# Adafruit_VL53L0X.net
KiCad netlist of a schematic drawn in EAGLE
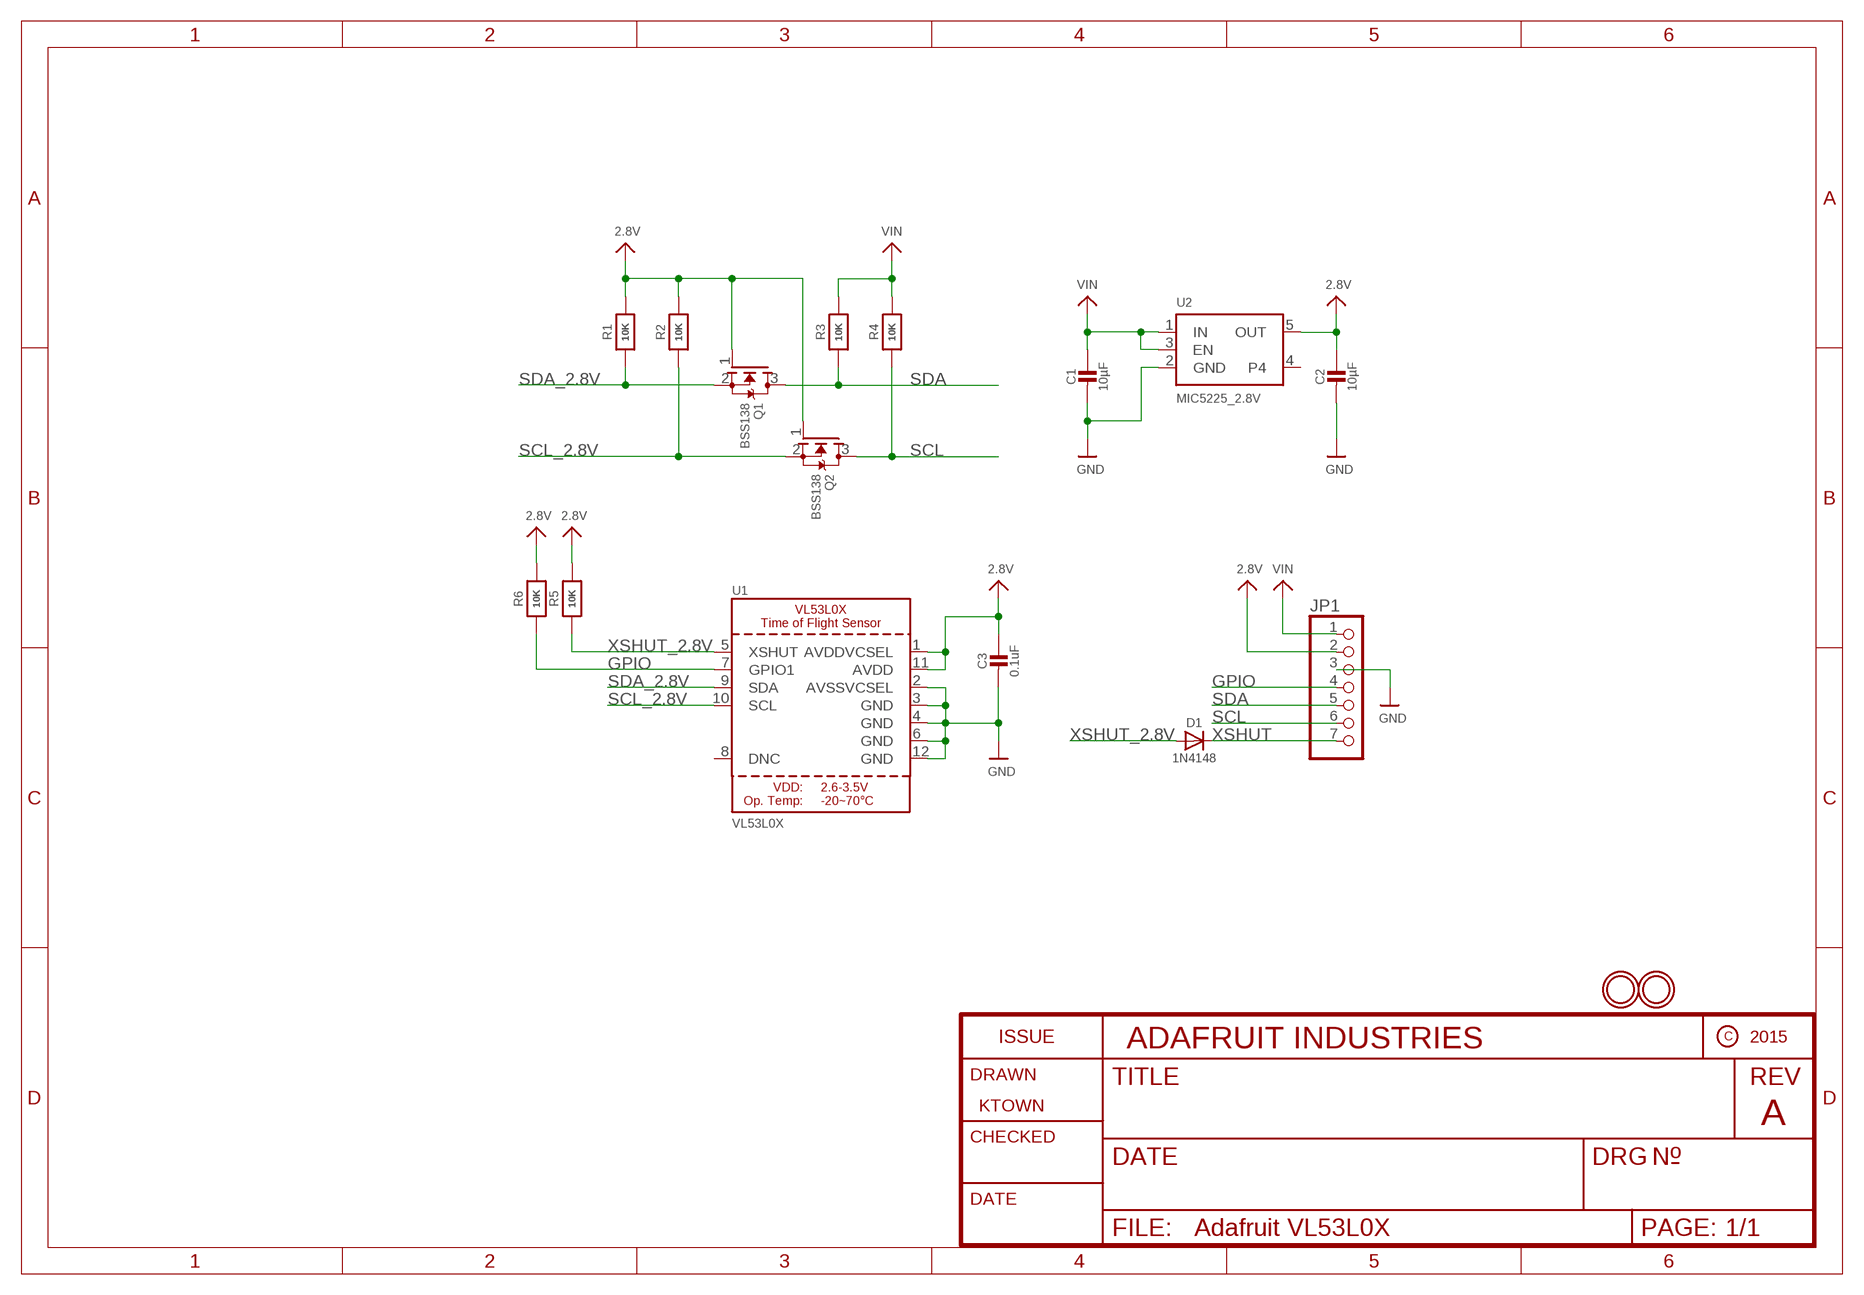
[diagram p0: schematic, sheet 1]

(export (version "E")
  (design (tool "Eeschema 10.0.6"))
  (components
    (comp (ref "C1")
      (value "10µF")
      (footprint "eagle-import:0805-NO")
      (libsource (lib "eagle-import") (part "CAP_CERAMIC0805-NOOUTLINE"))
    )
    (comp (ref "C2")
      (value "10µF")
      (footprint "eagle-import:0805-NO")
      (libsource (lib "eagle-import") (part "CAP_CERAMIC0805-NOOUTLINE"))
    )
    (comp (ref "C3")
      (value "0.1uF")
      (footprint "eagle-import:0805-NO")
      (libsource (lib "eagle-import") (part "CAP_CERAMIC0805-NOOUTLINE"))
    )
    (comp (ref "D1")
      (value "1N4148")
      (footprint "eagle-import:SOD-323")
      (libsource (lib "eagle-import") (part "DIODESOD-323"))
    )
    (comp (ref "JP1")
      (value "HEADER-1X770MIL")
      (footprint "eagle-import:1X07_ROUND_70")
      (libsource (lib "eagle-import") (part "HEADER-1X770MIL"))
    )
    (comp (ref "Q1")
      (value "BSS138")
      (footprint "eagle-import:SOT23-WIDE")
      (libsource (lib "eagle-import") (part "MOSFET-NWIDE"))
    )
    (comp (ref "Q2")
      (value "BSS138")
      (footprint "eagle-import:SOT23-WIDE")
      (libsource (lib "eagle-import") (part "MOSFET-NWIDE"))
    )
    (comp (ref "R1")
      (value "10K")
      (footprint "eagle-import:0805-NO")
      (libsource (lib "eagle-import") (part "RESISTOR0805_NOOUTLINE"))
    )
    (comp (ref "R2")
      (value "10K")
      (footprint "eagle-import:0805-NO")
      (libsource (lib "eagle-import") (part "RESISTOR0805_NOOUTLINE"))
    )
    (comp (ref "R3")
      (value "10K")
      (footprint "eagle-import:0805-NO")
      (libsource (lib "eagle-import") (part "RESISTOR0805_NOOUTLINE"))
    )
    (comp (ref "R4")
      (value "10K")
      (footprint "eagle-import:0805-NO")
      (libsource (lib "eagle-import") (part "RESISTOR0805_NOOUTLINE"))
    )
    (comp (ref "R5")
      (value "10K")
      (footprint "eagle-import:0805-NO")
      (libsource (lib "eagle-import") (part "RESISTOR0805_NOOUTLINE"))
    )
    (comp (ref "R6")
      (value "10K")
      (footprint "eagle-import:0805-NO")
      (libsource (lib "eagle-import") (part "RESISTOR0805_NOOUTLINE"))
    )
    (comp (ref "U$13")
      (value "MOUNTINGHOLE2.5")
      (footprint "eagle-import:MOUNTINGHOLE_2.5_PLATED")
      (libsource (lib "eagle-import") (part "MOUNTINGHOLE2.5"))
    )
    (comp (ref "U$14")
      (value "MOUNTINGHOLE2.5")
      (footprint "eagle-import:MOUNTINGHOLE_2.5_PLATED")
      (libsource (lib "eagle-import") (part "MOUNTINGHOLE2.5"))
    )
    (comp (ref "U1")
      (value "VL53L0X")
      (footprint "eagle-import:LGA12_ST")
      (libsource (lib "eagle-import") (part "VL53L0X"))
    )
    (comp (ref "U2")
      (value "MIC5225_2.8V")
      (footprint "eagle-import:SOT23-5")
      (libsource (lib "eagle-import") (part "VREG_SOT23-5"))
    )
  )
  (nets
    (net (code "1") (name "/GPIO") (class "Default")
      (node (ref "JP1") (pin "4") (pinfunction "4_4") (pintype "passive"))
      (node (ref "R6") (pin "1") (pinfunction "1_1") (pintype "passive"))
      (node (ref "U1") (pin "7") (pinfunction "GPIO1_7") (pintype "output"))
    )
    (net (code "2") (name "/SCL") (class "Default")
      (node (ref "JP1") (pin "6") (pinfunction "6_6") (pintype "passive"))
      (node (ref "Q2") (pin "3") (pinfunction "D_3") (pintype "bidirectional"))
      (node (ref "R4") (pin "1") (pinfunction "1_1") (pintype "passive"))
    )
    (net (code "3") (name "/SCL_2.8V") (class "Default")
      (node (ref "Q2") (pin "2") (pinfunction "S_2") (pintype "bidirectional"))
      (node (ref "R2") (pin "1") (pinfunction "1_1") (pintype "passive"))
      (node (ref "U1") (pin "10") (pinfunction "SCL_10") (pintype "open_collector"))
    )
    (net (code "4") (name "/SDA") (class "Default")
      (node (ref "JP1") (pin "5") (pinfunction "5_5") (pintype "passive"))
      (node (ref "Q1") (pin "3") (pinfunction "D_3") (pintype "bidirectional"))
      (node (ref "R3") (pin "1") (pinfunction "1_1") (pintype "passive"))
    )
    (net (code "5") (name "/SDA_2.8V") (class "Default")
      (node (ref "Q1") (pin "2") (pinfunction "S_2") (pintype "bidirectional"))
      (node (ref "R1") (pin "1") (pinfunction "1_1") (pintype "passive"))
      (node (ref "U1") (pin "9") (pinfunction "SDA_9") (pintype "open_collector"))
    )
    (net (code "6") (name "/XSHUT") (class "Default")
      (node (ref "D1") (pin "C") (pinfunction "C_C") (pintype "passive"))
      (node (ref "JP1") (pin "7") (pinfunction "7_7") (pintype "passive"))
    )
    (net (code "7") (name "/XSHUT_2.8V") (class "Default")
      (node (ref "D1") (pin "A") (pinfunction "A_A") (pintype "passive"))
      (node (ref "R5") (pin "1") (pinfunction "1_1") (pintype "passive"))
      (node (ref "U1") (pin "5") (pinfunction "XSHUT_5") (pintype "input"))
    )
    (net (code "8") (name "2.8V") (class "Default")
      (node (ref "C2") (pin "1") (pinfunction "1_1") (pintype "passive"))
      (node (ref "C3") (pin "1") (pinfunction "1_1") (pintype "passive"))
      (node (ref "JP1") (pin "2") (pinfunction "2_2") (pintype "passive"))
      (node (ref "Q1") (pin "1") (pinfunction "G_1") (pintype "bidirectional"))
      (node (ref "Q2") (pin "1") (pinfunction "G_1") (pintype "bidirectional"))
      (node (ref "R1") (pin "2") (pinfunction "2_2") (pintype "passive"))
      (node (ref "R2") (pin "2") (pinfunction "2_2") (pintype "passive"))
      (node (ref "R5") (pin "2") (pinfunction "2_2") (pintype "passive"))
      (node (ref "R6") (pin "2") (pinfunction "2_2") (pintype "passive"))
      (node (ref "U1") (pin "1") (pinfunction "AVDDVCSEL_1") (pintype "power_in"))
      (node (ref "U1") (pin "11") (pinfunction "AVDD_11") (pintype "power_in"))
      (node (ref "U2") (pin "5") (pinfunction "OUT_5") (pintype "power_in"))
    )
    (net (code "9") (name "GND") (class "Default")
      (node (ref "C1") (pin "2") (pinfunction "2_2") (pintype "passive"))
      (node (ref "C2") (pin "2") (pinfunction "2_2") (pintype "passive"))
      (node (ref "C3") (pin "2") (pinfunction "2_2") (pintype "passive"))
      (node (ref "JP1") (pin "3") (pinfunction "3_3") (pintype "passive"))
      (node (ref "U1") (pin "12") (pinfunction "GND_12") (pintype "power_in"))
      (node (ref "U1") (pin "2") (pinfunction "AVSSVCSEL_2") (pintype "power_in"))
      (node (ref "U1") (pin "3") (pinfunction "GND_3") (pintype "power_in"))
      (node (ref "U1") (pin "4") (pinfunction "GND_4") (pintype "power_in"))
      (node (ref "U1") (pin "6") (pinfunction "GND_6") (pintype "power_in"))
      (node (ref "U2") (pin "2") (pinfunction "GND_2") (pintype "power_in"))
    )
    (net (code "10") (name "VIN") (class "Default")
      (node (ref "C1") (pin "1") (pinfunction "1_1") (pintype "passive"))
      (node (ref "JP1") (pin "1") (pinfunction "1_1") (pintype "passive"))
      (node (ref "R3") (pin "2") (pinfunction "2_2") (pintype "passive"))
      (node (ref "R4") (pin "2") (pinfunction "2_2") (pintype "passive"))
      (node (ref "U2") (pin "1") (pinfunction "IN_1") (pintype "power_in"))
      (node (ref "U2") (pin "3") (pinfunction "EN_3") (pintype "input"))
    )
    (net (code "11") (name "unconnected-(U1-DNC-Pad8)") (class "Default")
      (node (ref "U1") (pin "8") (pinfunction "DNC_8") (pintype "no_connect"))
    )
    (net (code "12") (name "unconnected-(U2-P4-Pad4)") (class "Default")
      (node (ref "U2") (pin "4") (pinfunction "P4_4") (pintype "bidirectional"))
    )
  )
)
